# mcu.net
KiCad netlist of a schematic drawn in Altium Designer
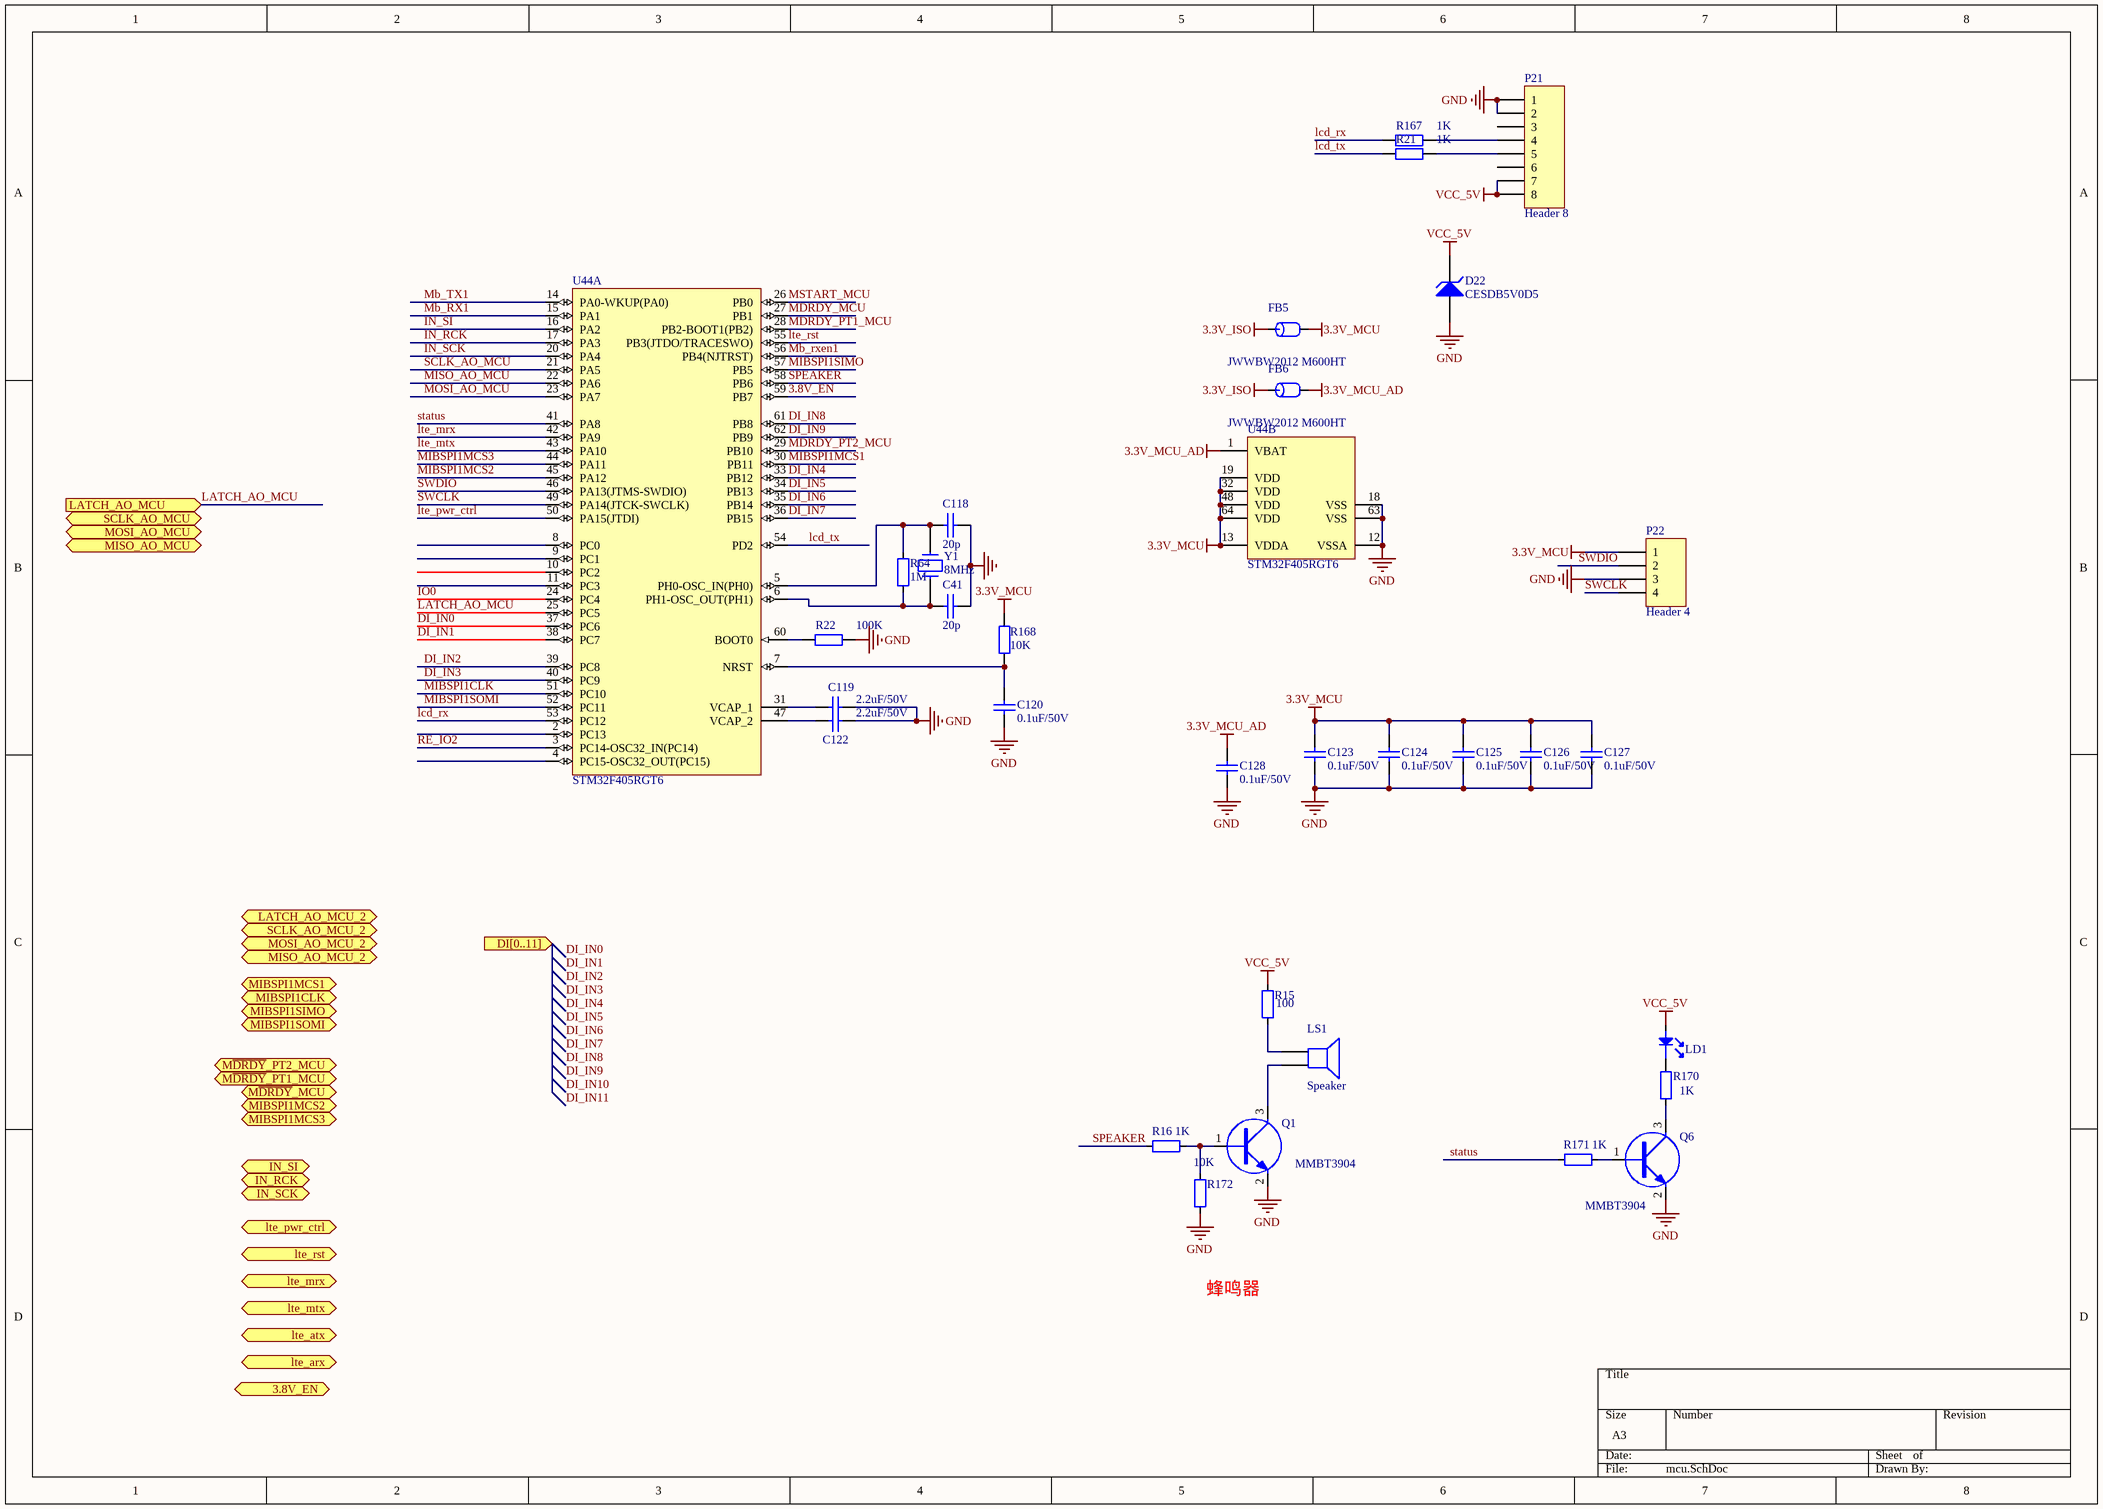
[diagram p0: mcu.SchDoc]

(export (version "E")
  (design (tool "Eeschema 10.0.6"))
  (components
    (comp (ref "C41")
      (value "20p")
      (footprint "0603c")
      (description "Capacitor")
      (libsource (lib "Schlib") (part "CAP"))
    )
    (comp (ref "C118")
      (value "20p")
      (footprint "0603c")
      (description "Capacitor")
      (libsource (lib "Schlib") (part "CAP"))
    )
    (comp (ref "C119")
      (value "2.2uF/50V")
      (footprint "0603C")
      (description "Capacitor")
      (fields (field (name "PUBLISHER") "Altium Limited"))
      (libsource (lib "Miscellaneous Devices") (part "Cap"))
    )
    (comp (ref "C120")
      (value "0.1uF/50V")
      (footprint "0603C")
      (description "Capacitor")
      (fields (field (name "PUBLISHER") "Altium Limited"))
      (libsource (lib "Miscellaneous Devices") (part "Cap"))
    )
    (comp (ref "C122")
      (value "2.2uF/50V")
      (footprint "0603C")
      (description "Capacitor")
      (fields (field (name "PUBLISHER") "Altium Limited"))
      (libsource (lib "Miscellaneous Devices") (part "Cap"))
    )
    (comp (ref "C123")
      (value "0.1uF/50V")
      (footprint "0603C")
      (description "Capacitor")
      (fields (field (name "PUBLISHER") "Altium Limited"))
      (libsource (lib "Miscellaneous Devices") (part "Cap"))
    )
    (comp (ref "C124")
      (value "0.1uF/50V")
      (footprint "0603C")
      (description "Capacitor")
      (fields (field (name "PUBLISHER") "Altium Limited"))
      (libsource (lib "Miscellaneous Devices") (part "Cap"))
    )
    (comp (ref "C125")
      (value "0.1uF/50V")
      (footprint "0603C")
      (description "Capacitor")
      (fields (field (name "PUBLISHER") "Altium Limited"))
      (libsource (lib "Miscellaneous Devices") (part "Cap"))
    )
    (comp (ref "C126")
      (value "0.1uF/50V")
      (footprint "0603C")
      (description "Capacitor")
      (fields (field (name "PUBLISHER") "Altium Limited"))
      (libsource (lib "Miscellaneous Devices") (part "Cap"))
    )
    (comp (ref "C127")
      (value "0.1uF/50V")
      (footprint "0603C")
      (description "Capacitor")
      (fields (field (name "PUBLISHER") "Altium Limited"))
      (libsource (lib "Miscellaneous Devices") (part "Cap"))
    )
    (comp (ref "C128")
      (value "0.1uF/50V")
      (footprint "0603C")
      (description "Capacitor")
      (fields (field (name "PUBLISHER") "Altium Limited"))
      (libsource (lib "Miscellaneous Devices") (part "Cap"))
    )
    (comp (ref "D22")
      (value "CESDB5V0D5")
      (footprint "sod323")
      (description "Zener Diode")
      (fields (field (name "PUBLISHER") "Altium Limited"))
      (libsource (lib "Miscellaneous Devices") (part "D Zener"))
    )
    (comp (ref "FB5")
      (value "JWWBW2012 M600HT")
      (footprint "0805R")
      (libsource (lib "Schlib_20110825") (part "FB"))
    )
    (comp (ref "FB6")
      (value "JWWBW2012 M600HT")
      (footprint "0805R")
      (libsource (lib "Schlib_20110825") (part "FB"))
    )
    (comp (ref "LD1")
      (value "LED_Green_19-217")
      (footprint "0603led")
      (libsource (lib "RC_M_D_00") (part "LED_Green_19-217"))
    )
    (comp (ref "LS1")
      (value "Speaker")
      (footprint "BUFFER_0905")
      (description "Loudspeaker")
      (fields (field (name "PUBLISHER") "Altium Limited"))
      (libsource (lib "Miscellaneous Devices") (part "Speaker"))
    )
    (comp (ref "P21")
      (value "Header 8")
      (footprint "2.0x8")
      (description "Header, 8-Pin")
      (fields (field (name "PUBLISHER") "Altium Limited"))
      (libsource (lib "Miscellaneous Connectors") (part "Header 8"))
    )
    (comp (ref "P22")
      (value "Header 4")
      (footprint "HDR1X4")
      (description "Header, 4-Pin")
      (fields (field (name "PUBLISHER") "Altium Limited"))
      (libsource (lib "Miscellaneous Connectors") (part "Header 4"))
    )
    (comp (ref "Q1")
      (value "MMBT3904")
      (footprint "SOT23-3")
      (libsource (lib "CenLib") (part "NPN_MMBT3904"))
    )
    (comp (ref "Q6")
      (value "MMBT3904")
      (footprint "SOT23-3")
      (libsource (lib "CenLib") (part "NPN_MMBT3904"))
    )
    (comp (ref "R15") (value "100") (footprint "0603R") (libsource (lib "RC_M_D_00") (part "RES0603")))
    (comp (ref "R16") (value "1K") (footprint "0603r") (libsource (lib "RC_M_D_00") (part "RES0603")))
    (comp (ref "R21") (value "1K") (footprint "0603R") (libsource (lib "") (part "Res0805M_1")))
    (comp (ref "R22") (value "100K") (footprint "0603R") (libsource (lib "") (part "Res0805M_1")))
    (comp (ref "R64") (value "1M") (footprint "0603R") (libsource (lib "RC_M_D_00") (part "RES0603")))
    (comp (ref "R167") (value "1K") (footprint "0603R") (libsource (lib "") (part "Res0805M_1")))
    (comp (ref "R168") (value "10K") (footprint "0603R") (libsource (lib "MQlibrary") (part "Res0805M")))
    (comp (ref "R170") (value "1K") (footprint "0603r") (libsource (lib "RC_M_D_00") (part "RES0603")))
    (comp (ref "R171") (value "1K") (footprint "0603r") (libsource (lib "RC_M_D_00") (part "RES0603")))
    (comp (ref "R172") (value "10K") (footprint "0603r") (libsource (lib "RC_M_D_00") (part "RES0603")))
    (comp (ref "U44")
      (value "STM32F405RGT6")
      (footprint "STM-LQFP64_N")
      (fields (field (name "MANUFACTURER") "STMicroelectronics"))
      (libsource (lib "STMicroelectronics STM32 F4") (part "STM32F405RGT6"))
    )
    (comp (ref "Y1")
      (value "8MHz")
      (footprint "CRAY_5032")
      (description "HC49S-8MHz")
      (libsource (lib "*") (part "CRYSTAL"))
    )
  )
  (nets
    (net (code "13") (name "/3.8V_EN") (class "Default")
      (node (ref "U44") (pin "59") (pinfunction "PB7_59") (pintype "bidirectional"))
    )
    (net (code "15") (name "/DI_IN0") (class "Default")
      (node (ref "U44") (pin "37") (pinfunction "PC6_37") (pintype "bidirectional"))
    )
    (net (code "16") (name "/DI_IN1") (class "Default")
      (node (ref "U44") (pin "38") (pinfunction "PC7_38") (pintype "bidirectional"))
    )
    (net (code "17") (name "/DI_IN2") (class "Default")
      (node (ref "U44") (pin "39") (pinfunction "PC8_39") (pintype "bidirectional"))
    )
    (net (code "18") (name "/DI_IN3") (class "Default")
      (node (ref "U44") (pin "40") (pinfunction "PC9_40") (pintype "bidirectional"))
    )
    (net (code "19") (name "/DI_IN4") (class "Default")
      (node (ref "U44") (pin "33") (pinfunction "PB12_33") (pintype "bidirectional"))
    )
    (net (code "20") (name "/DI_IN5") (class "Default")
      (node (ref "U44") (pin "34") (pinfunction "PB13_34") (pintype "bidirectional"))
    )
    (net (code "21") (name "/DI_IN6") (class "Default")
      (node (ref "U44") (pin "35") (pinfunction "PB14_35") (pintype "bidirectional"))
    )
    (net (code "22") (name "/DI_IN7") (class "Default")
      (node (ref "U44") (pin "36") (pinfunction "PB15_36") (pintype "bidirectional"))
    )
    (net (code "23") (name "/DI_IN8") (class "Default")
      (node (ref "U44") (pin "61") (pinfunction "PB8_61") (pintype "bidirectional"))
    )
    (net (code "24") (name "/DI_IN9") (class "Default")
      (node (ref "U44") (pin "62") (pinfunction "PB9_62") (pintype "bidirectional"))
    )
    (net (code "27") (name "/IN_RCK") (class "Default")
      (node (ref "U44") (pin "17") (pinfunction "PA3_17") (pintype "bidirectional"))
    )
    (net (code "28") (name "/IN_SCK") (class "Default")
      (node (ref "U44") (pin "20") (pinfunction "PA4_20") (pintype "bidirectional"))
    )
    (net (code "29") (name "/IN_SI") (class "Default")
      (node (ref "U44") (pin "16") (pinfunction "PA2_16") (pintype "bidirectional"))
    )
    (net (code "30") (name "/IO0") (class "Default")
      (node (ref "U44") (pin "24") (pinfunction "PC4_24") (pintype "bidirectional"))
    )
    (net (code "31") (name "/LATCH_AO_MCU") (class "Default")
      (node (ref "U44") (pin "25") (pinfunction "PC5_25") (pintype "bidirectional"))
    )
    (net (code "33") (name "/MIBSPI1CLK") (class "Default")
      (node (ref "U44") (pin "51") (pinfunction "PC10_51") (pintype "bidirectional"))
    )
    (net (code "34") (name "/MIBSPI1MCS1") (class "Default")
      (node (ref "U44") (pin "30") (pinfunction "PB11_30") (pintype "bidirectional"))
    )
    (net (code "35") (name "/MIBSPI1MCS2") (class "Default")
      (node (ref "U44") (pin "45") (pinfunction "PA12_45") (pintype "bidirectional"))
    )
    (net (code "36") (name "/MIBSPI1MCS3") (class "Default")
      (node (ref "U44") (pin "44") (pinfunction "PA11_44") (pintype "bidirectional"))
    )
    (net (code "37") (name "/MIBSPI1SIMO") (class "Default")
      (node (ref "U44") (pin "57") (pinfunction "PB5_57") (pintype "bidirectional"))
    )
    (net (code "38") (name "/MIBSPI1SOMI") (class "Default")
      (node (ref "U44") (pin "52") (pinfunction "PC11_52") (pintype "bidirectional"))
    )
    (net (code "39") (name "/MISO_AO_MCU") (class "Default")
      (node (ref "U44") (pin "22") (pinfunction "PA6_22") (pintype "bidirectional"))
    )
    (net (code "41") (name "/MOSI_AO_MCU") (class "Default")
      (node (ref "U44") (pin "23") (pinfunction "PA7_23") (pintype "bidirectional"))
    )
    (net (code "43") (name "/MSTART_MCU") (class "Default")
      (node (ref "U44") (pin "26") (pinfunction "PB0_26") (pintype "bidirectional"))
    )
    (net (code "44") (name "/Mb_RX1") (class "Default")
      (node (ref "U44") (pin "15") (pinfunction "PA1_15") (pintype "bidirectional"))
    )
    (net (code "45") (name "/Mb_TX1") (class "Default")
      (node (ref "U44") (pin "14") (pinfunction "PA0-WKUP(PA0)_14") (pintype "bidirectional"))
    )
    (net (code "46") (name "/Mb_rxen1") (class "Default")
      (node (ref "U44") (pin "56") (pinfunction "PB4(NJTRST)_56") (pintype "bidirectional"))
    )
    (net (code "47") (name "/M~{DRDY}_MCU") (class "Default")
      (node (ref "U44") (pin "27") (pinfunction "PB1_27") (pintype "bidirectional"))
    )
    (net (code "48") (name "/M~{DRDY}_PT1_MCU") (class "Default")
      (node (ref "U44") (pin "28") (pinfunction "PB2-BOOT1(PB2)_28") (pintype "bidirectional"))
    )
    (net (code "49") (name "/M~{DRDY}_PT2_MCU") (class "Default")
      (node (ref "U44") (pin "29") (pinfunction "PB10_29") (pintype "bidirectional"))
    )
    (net (code "50") (name "/RE_IO2") (class "Default")
      (node (ref "U44") (pin "3") (pinfunction "PC14-OSC32_IN(PC14)_3") (pintype "bidirectional"))
    )
    (net (code "51") (name "/SCLK_AO_MCU") (class "Default")
      (node (ref "U44") (pin "21") (pinfunction "PA5_21") (pintype "bidirectional"))
    )
    (net (code "53") (name "/SPEAKER") (class "Default")
      (node (ref "R16") (pin "2") (pinfunction "2_2") (pintype "passive"))
      (node (ref "U44") (pin "58") (pinfunction "PB6_58") (pintype "bidirectional"))
    )
    (net (code "54") (name "/SWCLK") (class "Default")
      (node (ref "P22") (pin "4") (pinfunction "4_4") (pintype "passive"))
      (node (ref "U44") (pin "49") (pinfunction "PA14(JTCK-SWCLK)_49") (pintype "bidirectional"))
    )
    (net (code "55") (name "/SWDIO") (class "Default")
      (node (ref "P22") (pin "2") (pinfunction "2_2") (pintype "passive"))
      (node (ref "U44") (pin "46") (pinfunction "PA13(JTMS-SWDIO)_46") (pintype "bidirectional"))
    )
    (net (code "56") (name "/lcd_rx") (class "Default")
      (node (ref "R167") (pin "1") (pinfunction "1_1") (pintype "passive"))
      (node (ref "U44") (pin "53") (pinfunction "PC12_53") (pintype "bidirectional"))
    )
    (net (code "57") (name "/lcd_tx") (class "Default")
      (node (ref "R21") (pin "1") (pinfunction "1_1") (pintype "passive"))
      (node (ref "U44") (pin "54") (pinfunction "PD2_54") (pintype "bidirectional"))
    )
    (net (code "60") (name "/lte_mrx") (class "Default")
      (node (ref "U44") (pin "42") (pinfunction "PA9_42") (pintype "bidirectional"))
    )
    (net (code "61") (name "/lte_mtx") (class "Default")
      (node (ref "U44") (pin "43") (pinfunction "PA10_43") (pintype "bidirectional"))
    )
    (net (code "62") (name "/lte_pwr_ctrl") (class "Default")
      (node (ref "U44") (pin "50") (pinfunction "PA15(JTDI)_50") (pintype "bidirectional"))
    )
    (net (code "63") (name "/lte_rst") (class "Default")
      (node (ref "U44") (pin "55") (pinfunction "PB3(JTDO/TRACESWO)_55") (pintype "bidirectional"))
    )
    (net (code "64") (name "/status") (class "Default")
      (node (ref "R171") (pin "1") (pinfunction "1_1") (pintype "passive"))
      (node (ref "U44") (pin "41") (pinfunction "PA8_41") (pintype "bidirectional"))
    )
    (net (code "65") (name "3.3V_ISO") (class "Default")
      (node (ref "FB5") (pin "1") (pintype "passive"))
      (node (ref "FB6") (pin "1") (pintype "passive"))
    )
    (net (code "66") (name "3.3V_MCU") (class "Default")
      (node (ref "C123") (pin "2") (pinfunction "2_2") (pintype "passive"))
      (node (ref "C124") (pin "2") (pinfunction "2_2") (pintype "passive"))
      (node (ref "C125") (pin "2") (pinfunction "2_2") (pintype "passive"))
      (node (ref "C126") (pin "2") (pinfunction "2_2") (pintype "passive"))
      (node (ref "C127") (pin "2") (pinfunction "2_2") (pintype "passive"))
      (node (ref "FB5") (pin "2") (pintype "passive"))
      (node (ref "P22") (pin "1") (pinfunction "1_1") (pintype "passive"))
      (node (ref "R168") (pin "2") (pinfunction "2_2") (pintype "passive"))
      (node (ref "U44") (pin "13") (pinfunction "VDDA_13") (pintype "power_in"))
      (node (ref "U44") (pin "19") (pinfunction "VDD_19") (pintype "power_in"))
      (node (ref "U44") (pin "32") (pinfunction "VDD_32") (pintype "power_in"))
      (node (ref "U44") (pin "48") (pinfunction "VDD_48") (pintype "power_in"))
      (node (ref "U44") (pin "64") (pinfunction "VDD_64") (pintype "power_in"))
    )
    (net (code "67") (name "3.3V_MCU_AD") (class "Default")
      (node (ref "C128") (pin "2") (pinfunction "2_2") (pintype "passive"))
      (node (ref "FB6") (pin "2") (pintype "passive"))
      (node (ref "U44") (pin "1") (pinfunction "VBAT_1") (pintype "power_in"))
    )
    (net (code "68") (name "GND") (class "Default")
      (node (ref "C118") (pin "1") (pinfunction "1_1") (pintype "passive"))
      (node (ref "C119") (pin "1") (pinfunction "1_1") (pintype "passive"))
      (node (ref "C120") (pin "1") (pinfunction "1_1") (pintype "passive"))
      (node (ref "C122") (pin "1") (pinfunction "1_1") (pintype "passive"))
      (node (ref "C123") (pin "1") (pinfunction "1_1") (pintype "passive"))
      (node (ref "C124") (pin "1") (pinfunction "1_1") (pintype "passive"))
      (node (ref "C125") (pin "1") (pinfunction "1_1") (pintype "passive"))
      (node (ref "C126") (pin "1") (pinfunction "1_1") (pintype "passive"))
      (node (ref "C127") (pin "1") (pinfunction "1_1") (pintype "passive"))
      (node (ref "C128") (pin "1") (pinfunction "1_1") (pintype "passive"))
      (node (ref "C41") (pin "1") (pinfunction "1_1") (pintype "passive"))
      (node (ref "D22") (pin "1") (pinfunction "A_1") (pintype "passive"))
      (node (ref "P21") (pin "1") (pinfunction "1_1") (pintype "passive"))
      (node (ref "P21") (pin "2") (pinfunction "2_2") (pintype "passive"))
      (node (ref "P22") (pin "3") (pinfunction "3_3") (pintype "passive"))
      (node (ref "Q1") (pin "2") (pinfunction "E_2") (pintype "passive"))
      (node (ref "Q6") (pin "2") (pinfunction "E_2") (pintype "passive"))
      (node (ref "R172") (pin "2") (pinfunction "2_2") (pintype "passive"))
      (node (ref "R22") (pin "2") (pinfunction "2_2") (pintype "passive"))
      (node (ref "U44") (pin "12") (pinfunction "VSSA_12") (pintype "power_in"))
      (node (ref "U44") (pin "18") (pinfunction "VSS_18") (pintype "power_in"))
      (node (ref "U44") (pin "63") (pinfunction "VSS_63") (pintype "power_in"))
    )
    (net (code "69") (name "Net-(LD1-Pad2)") (class "Default")
      (node (ref "LD1") (pin "2") (pinfunction "2_2") (pintype "passive"))
      (node (ref "R170") (pin "1") (pinfunction "1_1") (pintype "passive"))
    )
    (net (code "70") (name "Net-(LS1-Pad1)") (class "Default")
      (node (ref "LS1") (pin "1") (pinfunction "1_1") (pintype "passive"))
      (node (ref "R15") (pin "2") (pinfunction "2_2") (pintype "passive"))
    )
    (net (code "71") (name "Net-(P21-Pad4)") (class "Default")
      (node (ref "P21") (pin "4") (pinfunction "4_4") (pintype "passive"))
      (node (ref "R167") (pin "2") (pinfunction "2_2") (pintype "passive"))
    )
    (net (code "72") (name "Net-(P21-Pad5)") (class "Default")
      (node (ref "P21") (pin "5") (pinfunction "5_5") (pintype "passive"))
      (node (ref "R21") (pin "2") (pinfunction "2_2") (pintype "passive"))
    )
    (net (code "73") (name "Net-(Q1-B)") (class "Default")
      (node (ref "Q1") (pin "1") (pinfunction "B_1") (pintype "passive"))
      (node (ref "R16") (pin "1") (pinfunction "1_1") (pintype "passive"))
      (node (ref "R172") (pin "1") (pinfunction "1_1") (pintype "passive"))
    )
    (net (code "74") (name "Net-(Q1-C)") (class "Default")
      (node (ref "LS1") (pin "2") (pinfunction "2_2") (pintype "passive"))
      (node (ref "Q1") (pin "3") (pinfunction "C_3") (pintype "passive"))
    )
    (net (code "75") (name "Net-(Q6-B)") (class "Default")
      (node (ref "Q6") (pin "1") (pinfunction "B_1") (pintype "passive"))
      (node (ref "R171") (pin "2") (pinfunction "2_2") (pintype "passive"))
    )
    (net (code "76") (name "Net-(Q6-C)") (class "Default")
      (node (ref "Q6") (pin "3") (pinfunction "C_3") (pintype "passive"))
      (node (ref "R170") (pin "2") (pinfunction "2_2") (pintype "passive"))
    )
    (net (code "77") (name "Net-(U44A-BOOT0)") (class "Default")
      (node (ref "R22") (pin "1") (pinfunction "1_1") (pintype "passive"))
      (node (ref "U44") (pin "60") (pinfunction "BOOT0_60") (pintype "input"))
    )
    (net (code "78") (name "Net-(U44A-NRST)") (class "Default")
      (node (ref "C120") (pin "2") (pinfunction "2_2") (pintype "passive"))
      (node (ref "R168") (pin "1") (pinfunction "1_1") (pintype "passive"))
      (node (ref "U44") (pin "7") (pinfunction "NRST_7") (pintype "bidirectional"))
    )
    (net (code "79") (name "Net-(U44A-PH0-OSC_IN(PH0))") (class "Default")
      (node (ref "C118") (pin "2") (pinfunction "2_2") (pintype "passive"))
      (node (ref "R64") (pin "2") (pinfunction "2_2") (pintype "passive"))
      (node (ref "U44") (pin "5") (pinfunction "PH0-OSC_IN(PH0)_5") (pintype "bidirectional"))
      (node (ref "Y1") (pin "1") (pinfunction "1_1") (pintype "passive"))
    )
    (net (code "80") (name "Net-(U44A-PH1-OSC_OUT(PH1))") (class "Default")
      (node (ref "C41") (pin "2") (pinfunction "2_2") (pintype "passive"))
      (node (ref "R64") (pin "1") (pinfunction "1_1") (pintype "passive"))
      (node (ref "U44") (pin "6") (pinfunction "PH1-OSC_OUT(PH1)_6") (pintype "bidirectional"))
      (node (ref "Y1") (pin "2") (pinfunction "2_2") (pintype "passive"))
    )
    (net (code "81") (name "Net-(U44A-VCAP_1)") (class "Default")
      (node (ref "C119") (pin "2") (pinfunction "2_2") (pintype "passive"))
      (node (ref "U44") (pin "31") (pinfunction "VCAP_1_31") (pintype "power_in"))
    )
    (net (code "82") (name "Net-(U44A-VCAP_2)") (class "Default")
      (node (ref "C122") (pin "2") (pinfunction "2_2") (pintype "passive"))
      (node (ref "U44") (pin "47") (pinfunction "VCAP_2_47") (pintype "power_in"))
    )
    (net (code "83") (name "VCC_5V") (class "Default")
      (node (ref "D22") (pin "2") (pinfunction "K_2") (pintype "passive"))
      (node (ref "LD1") (pin "1") (pinfunction "1_1") (pintype "passive"))
      (node (ref "P21") (pin "7") (pinfunction "7_7") (pintype "passive"))
      (node (ref "P21") (pin "8") (pinfunction "8_8") (pintype "passive"))
      (node (ref "R15") (pin "1") (pinfunction "1_1") (pintype "passive"))
    )
    (net (code "84") (name "unconnected-(P21-Pad3)") (class "Default")
      (node (ref "P21") (pin "3") (pinfunction "3_3") (pintype "passive"))
    )
    (net (code "85") (name "unconnected-(P21-Pad6)") (class "Default")
      (node (ref "P21") (pin "6") (pinfunction "6_6") (pintype "passive"))
    )
    (net (code "86") (name "unconnected-(U44A-PC0-Pad8)") (class "Default")
      (node (ref "U44") (pin "8") (pinfunction "PC0_8") (pintype "bidirectional"))
    )
    (net (code "87") (name "unconnected-(U44A-PC1-Pad9)") (class "Default")
      (node (ref "U44") (pin "9") (pinfunction "PC1_9") (pintype "bidirectional"))
    )
    (net (code "88") (name "unconnected-(U44A-PC2-Pad10)") (class "Default")
      (node (ref "U44") (pin "10") (pinfunction "PC2_10") (pintype "bidirectional"))
    )
    (net (code "89") (name "unconnected-(U44A-PC3-Pad11)") (class "Default")
      (node (ref "U44") (pin "11") (pinfunction "PC3_11") (pintype "bidirectional"))
    )
    (net (code "90") (name "unconnected-(U44A-PC13-Pad2)") (class "Default")
      (node (ref "U44") (pin "2") (pinfunction "PC13_2") (pintype "bidirectional"))
    )
    (net (code "91") (name "unconnected-(U44A-PC15-OSC32_OUT(PC15)-Pad4)") (class "Default")
      (node (ref "U44") (pin "4") (pinfunction "PC15-OSC32_OUT(PC15)_4") (pintype "bidirectional"))
    )
  )
)
